# Isolator_Gate_Driver.net
KiCad netlist of a schematic drawn in Altium Designer
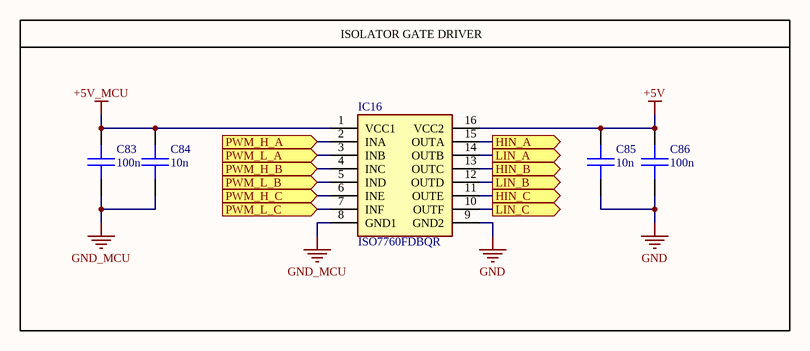
[diagram p0: Isolator_Gate_Driver.SchDoc]

(export (version "E")
  (design (tool "Eeschema 10.0.6"))
  (components
    (comp (ref "C83")
      (value "100n")
      (footprint "C_0603")
      (description "SMD Chip Capacitor")
      (libsource (lib "My_Integrated_Lib") (part "CAP"))
    )
    (comp (ref "C84")
      (value "10n")
      (footprint "C_0603")
      (description "SMD Chip Capacitor")
      (libsource (lib "My_Integrated_Lib") (part "CAP"))
    )
    (comp (ref "C85")
      (value "10n")
      (footprint "C_0603")
      (description "SMD Chip Capacitor")
      (libsource (lib "My_Integrated_Lib") (part "CAP"))
    )
    (comp (ref "C86")
      (value "100n")
      (footprint "C_0603")
      (description "SMD Chip Capacitor")
      (libsource (lib "My_Integrated_Lib") (part "CAP"))
    )
    (comp (ref "IC16")
      (value "ISO7760FDBQR")
      (footprint "SOP64P600X175-16N")
      (description "Integrated Circuit")
      (fields (field (name "MOUSER PART NUMBER") "595-ISO7760FDBQR"))
      (libsource (lib "My_Integrated_Lib") (part "ISO7760FDBQR"))
    )
  )
  (nets
    (net (code "1") (name "+5V") (class "Default")
      (node (ref "C85") (pin "2") (pinfunction "2_2") (pintype "passive"))
      (node (ref "C86") (pin "2") (pinfunction "2_2") (pintype "passive"))
      (node (ref "IC16") (pin "16") (pinfunction "VCC2_16") (pintype "passive"))
    )
    (net (code "2") (name "+5V_MCU") (class "Default")
      (node (ref "C83") (pin "2") (pinfunction "2_2") (pintype "passive"))
      (node (ref "C84") (pin "2") (pinfunction "2_2") (pintype "passive"))
      (node (ref "IC16") (pin "1") (pinfunction "VCC1_1") (pintype "passive"))
    )
    (net (code "3") (name "/HIN_A") (class "Default")
      (node (ref "IC16") (pin "15") (pinfunction "OUTA_15") (pintype "passive"))
    )
    (net (code "4") (name "/HIN_B") (class "Default")
      (node (ref "IC16") (pin "13") (pinfunction "OUTC_13") (pintype "passive"))
    )
    (net (code "5") (name "/HIN_C") (class "Default")
      (node (ref "IC16") (pin "11") (pinfunction "OUTE_11") (pintype "passive"))
    )
    (net (code "6") (name "/LIN_A") (class "Default")
      (node (ref "IC16") (pin "14") (pinfunction "OUTB_14") (pintype "passive"))
    )
    (net (code "7") (name "/LIN_B") (class "Default")
      (node (ref "IC16") (pin "12") (pinfunction "OUTD_12") (pintype "passive"))
    )
    (net (code "8") (name "/LIN_C") (class "Default")
      (node (ref "IC16") (pin "10") (pinfunction "OUTF_10") (pintype "passive"))
    )
    (net (code "9") (name "/PWM_H_A") (class "Default")
      (node (ref "IC16") (pin "2") (pinfunction "INA_2") (pintype "passive"))
    )
    (net (code "10") (name "/PWM_H_B") (class "Default")
      (node (ref "IC16") (pin "4") (pinfunction "INC_4") (pintype "passive"))
    )
    (net (code "11") (name "/PWM_H_C") (class "Default")
      (node (ref "IC16") (pin "6") (pinfunction "INE_6") (pintype "passive"))
    )
    (net (code "12") (name "/PWM_L_A") (class "Default")
      (node (ref "IC16") (pin "3") (pinfunction "INB_3") (pintype "passive"))
    )
    (net (code "13") (name "/PWM_L_B") (class "Default")
      (node (ref "IC16") (pin "5") (pinfunction "IND_5") (pintype "passive"))
    )
    (net (code "14") (name "/PWM_L_C") (class "Default")
      (node (ref "IC16") (pin "7") (pinfunction "INF_7") (pintype "passive"))
    )
    (net (code "15") (name "GND") (class "Default")
      (node (ref "C85") (pin "1") (pinfunction "1_1") (pintype "passive"))
      (node (ref "C86") (pin "1") (pinfunction "1_1") (pintype "passive"))
      (node (ref "IC16") (pin "9") (pinfunction "GND2_9") (pintype "passive"))
    )
    (net (code "16") (name "GND_MCU") (class "Default")
      (node (ref "C83") (pin "1") (pinfunction "1_1") (pintype "passive"))
      (node (ref "C84") (pin "1") (pinfunction "1_1") (pintype "passive"))
      (node (ref "IC16") (pin "8") (pinfunction "GND1_8") (pintype "passive"))
    )
  )
)
